# Filtro.net
KiCad netlist of a schematic drawn in Altium Designer
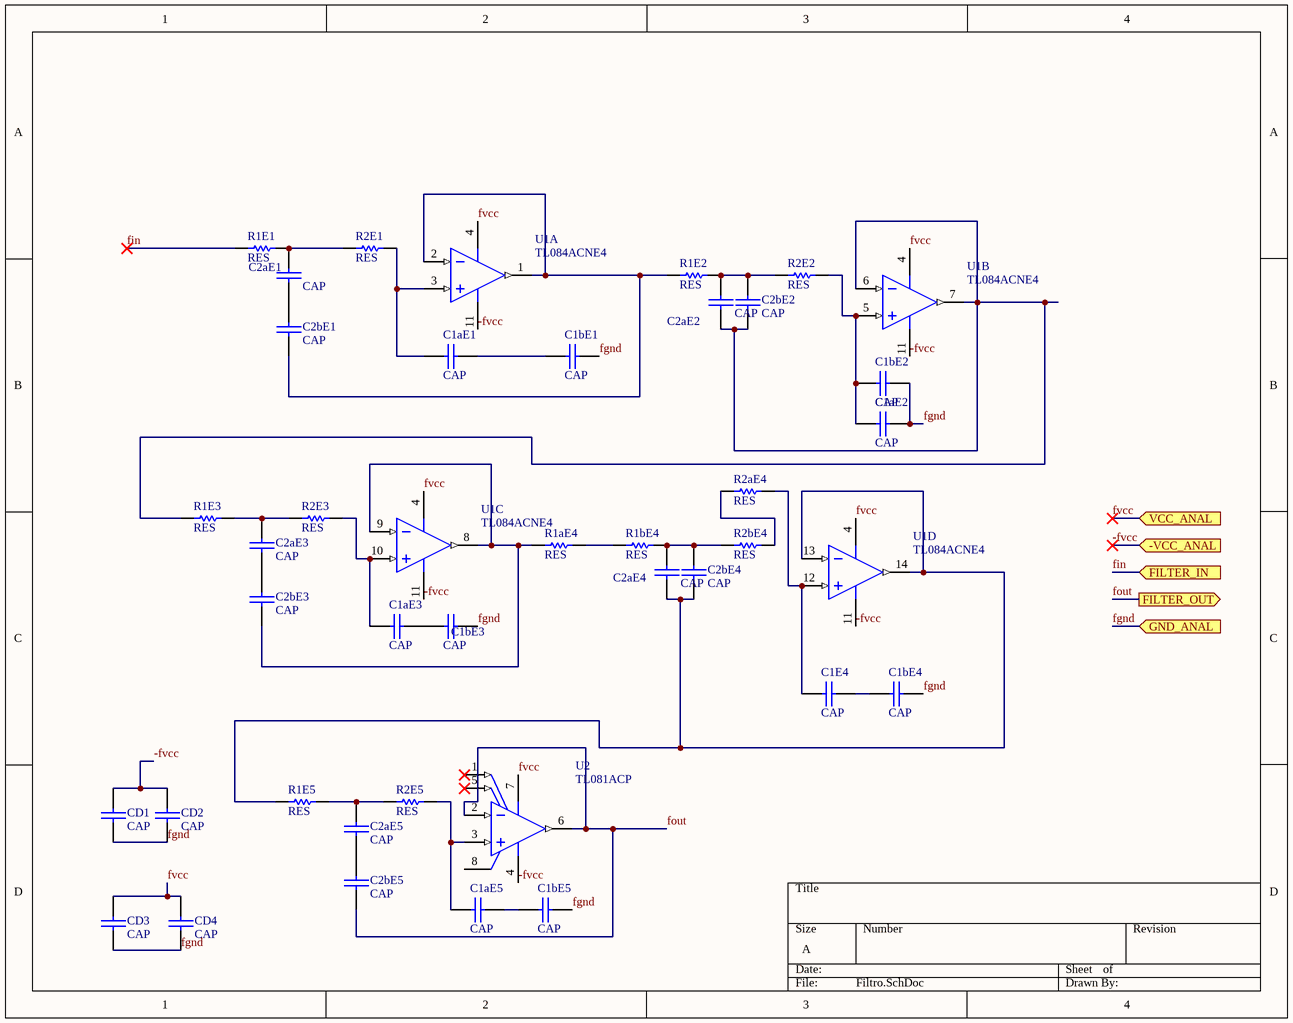
[diagram p0: Filtro.SchDoc]

(export (version "E")
  (design (tool "Eeschema 10.0.6"))
  (components
    (comp (ref "C1aE1") (value "CAP") (footprint "0805") (libsource (lib "LIB PIO IX") (part "CAP")))
    (comp (ref "C1aE2") (value "CAP") (footprint "0805") (libsource (lib "LIB PIO IX") (part "CAP")))
    (comp (ref "C1aE3") (value "CAP") (footprint "0805") (libsource (lib "LIB PIO IX") (part "CAP")))
    (comp (ref "C1aE5") (value "CAP") (footprint "0805") (libsource (lib "LIB PIO IX") (part "CAP")))
    (comp (ref "C1bE1") (value "CAP") (footprint "0805") (libsource (lib "LIB PIO IX") (part "CAP")))
    (comp (ref "C1bE2") (value "CAP") (footprint "0805") (libsource (lib "LIB PIO IX") (part "CAP")))
    (comp (ref "C1bE3") (value "CAP") (footprint "0805") (libsource (lib "LIB PIO IX") (part "CAP")))
    (comp (ref "C1bE4") (value "CAP") (footprint "0805") (libsource (lib "LIB PIO IX") (part "CAP")))
    (comp (ref "C1bE5") (value "CAP") (footprint "0805") (libsource (lib "LIB PIO IX") (part "CAP")))
    (comp (ref "C1E4") (value "CAP") (footprint "0805") (libsource (lib "LIB PIO IX") (part "CAP")))
    (comp (ref "C2aE1") (value "CAP") (footprint "0805") (libsource (lib "LIB PIO IX") (part "CAP")))
    (comp (ref "C2aE2") (value "CAP") (footprint "0805") (libsource (lib "LIB PIO IX") (part "CAP")))
    (comp (ref "C2aE3") (value "CAP") (footprint "0805") (libsource (lib "LIB PIO IX") (part "CAP")))
    (comp (ref "C2aE4") (value "CAP") (footprint "0805") (libsource (lib "LIB PIO IX") (part "CAP")))
    (comp (ref "C2aE5") (value "CAP") (footprint "0805") (libsource (lib "LIB PIO IX") (part "CAP")))
    (comp (ref "C2bE1") (value "CAP") (footprint "0805") (libsource (lib "LIB PIO IX") (part "CAP")))
    (comp (ref "C2bE2") (value "CAP") (footprint "0805") (libsource (lib "LIB PIO IX") (part "CAP")))
    (comp (ref "C2bE3") (value "CAP") (footprint "0805") (libsource (lib "LIB PIO IX") (part "CAP")))
    (comp (ref "C2bE4") (value "CAP") (footprint "0805") (libsource (lib "LIB PIO IX") (part "CAP")))
    (comp (ref "C2bE5") (value "CAP") (footprint "0805") (libsource (lib "LIB PIO IX") (part "CAP")))
    (comp (ref "CD1") (value "CAP") (footprint "0805") (libsource (lib "LIB PIO IX") (part "CAP")))
    (comp (ref "CD2") (value "CAP") (footprint "0805") (libsource (lib "LIB PIO IX") (part "CAP")))
    (comp (ref "CD3") (value "CAP") (footprint "0805") (libsource (lib "LIB PIO IX") (part "CAP")))
    (comp (ref "CD4") (value "CAP") (footprint "0805") (libsource (lib "LIB PIO IX") (part "CAP")))
    (comp (ref "R1aE4") (value "RES") (footprint "0805") (libsource (lib "LIB PIO IX") (part "RES")))
    (comp (ref "R1bE4") (value "RES") (footprint "0805") (libsource (lib "LIB PIO IX") (part "RES")))
    (comp (ref "R1E1") (value "RES") (footprint "0805") (libsource (lib "LIB PIO IX") (part "RES")))
    (comp (ref "R1E2") (value "RES") (footprint "0805") (libsource (lib "LIB PIO IX") (part "RES")))
    (comp (ref "R1E3") (value "RES") (footprint "0805") (libsource (lib "LIB PIO IX") (part "RES")))
    (comp (ref "R1E5") (value "RES") (footprint "0805") (libsource (lib "LIB PIO IX") (part "RES")))
    (comp (ref "R2aE4") (value "RES") (footprint "0805") (libsource (lib "LIB PIO IX") (part "RES")))
    (comp (ref "R2bE4") (value "RES") (footprint "0805") (libsource (lib "LIB PIO IX") (part "RES")))
    (comp (ref "R2E1") (value "RES") (footprint "0805") (libsource (lib "LIB PIO IX") (part "RES")))
    (comp (ref "R2E2") (value "RES") (footprint "0805") (libsource (lib "LIB PIO IX") (part "RES")))
    (comp (ref "R2E3") (value "RES") (footprint "0805") (libsource (lib "LIB PIO IX") (part "RES")))
    (comp (ref "R2E5") (value "RES") (footprint "0805") (libsource (lib "LIB PIO IX") (part "RES")))
    (comp (ref "U1")
      (value "TL084ACNE4")
      (footprint "TI-N14")
      (description "JFET-Input Operational Amplifier, 7 to 36 V, 0 to 70 degC, 14-pin DIP (N14), Pb-Free (RoHS)")
      (fields (field (name "MANUFACTURER") "Texas Instruments"))
      (libsource (lib "TI Amplifiers and Linear Operational Amplifier General Purpose") (part "TL084ACNE4"))
    )
    (comp (ref "U2")
      (value "TL081ACP")
      (footprint "TI-P8")
      (description "JFET-Input Operational Amplifier, 7 to 36 V, 0 to 70 degC, 8-pin DIP (P8), Pb-Free (RoHS)")
      (fields (field (name "MANUFACTURER") "Texas Instruments"))
      (libsource (lib "TI Amplifiers and Linear Operational Amplifier General Purpose") (part "TL081ACP"))
    )
  )
  (nets
    (net (code "1") (name "/-fvcc") (class "Default")
      (node (ref "CD1") (pin "1") (pinfunction "1_1") (pintype "passive"))
      (node (ref "CD2") (pin "1") (pinfunction "1_1") (pintype "passive"))
      (node (ref "U1") (pin "11") (pinfunction "VCC-_11") (pintype "power_in"))
      (node (ref "U2") (pin "4") (pinfunction "VCC-_4") (pintype "power_in"))
    )
    (net (code "2") (name "/fgnd") (class "Default")
      (node (ref "C1aE2") (pin "2") (pinfunction "2_2") (pintype "passive"))
      (node (ref "C1bE1") (pin "2") (pinfunction "2_2") (pintype "passive"))
      (node (ref "C1bE2") (pin "2") (pinfunction "2_2") (pintype "passive"))
      (node (ref "C1bE3") (pin "2") (pinfunction "2_2") (pintype "passive"))
      (node (ref "C1bE4") (pin "2") (pinfunction "2_2") (pintype "passive"))
      (node (ref "C1bE5") (pin "2") (pinfunction "2_2") (pintype "passive"))
      (node (ref "CD1") (pin "2") (pinfunction "2_2") (pintype "passive"))
      (node (ref "CD2") (pin "2") (pinfunction "2_2") (pintype "passive"))
      (node (ref "CD3") (pin "2") (pinfunction "2_2") (pintype "passive"))
      (node (ref "CD4") (pin "2") (pinfunction "2_2") (pintype "passive"))
    )
    (net (code "3") (name "/fin") (class "Default")
      (node (ref "R1E1") (pin "1") (pinfunction "1_1") (pintype "passive+no_connect"))
    )
    (net (code "4") (name "/fout") (class "Default")
      (node (ref "C2bE5") (pin "2") (pinfunction "2_2") (pintype "passive"))
      (node (ref "U2") (pin "2") (pinfunction "IN-_2") (pintype "input"))
      (node (ref "U2") (pin "6") (pinfunction "OUT_6") (pintype "output"))
    )
    (net (code "5") (name "/fvcc") (class "Default")
      (node (ref "CD3") (pin "1") (pinfunction "1_1") (pintype "passive"))
      (node (ref "CD4") (pin "1") (pinfunction "1_1") (pintype "passive"))
      (node (ref "U1") (pin "4") (pinfunction "VCC+_4") (pintype "power_in"))
      (node (ref "U2") (pin "7") (pinfunction "VCC+_7") (pintype "power_in"))
    )
    (net (code "6") (name "Net-(C1E4-Pad2)") (class "Default")
      (node (ref "C1E4") (pin "2") (pinfunction "2_2") (pintype "passive"))
      (node (ref "C1bE4") (pin "1") (pinfunction "1_1") (pintype "passive"))
    )
    (net (code "7") (name "Net-(C1aE1-Pad2)") (class "Default")
      (node (ref "C1aE1") (pin "2") (pinfunction "2_2") (pintype "passive"))
      (node (ref "C1bE1") (pin "1") (pinfunction "1_1") (pintype "passive"))
    )
    (net (code "8") (name "Net-(C1aE3-Pad2)") (class "Default")
      (node (ref "C1aE3") (pin "2") (pinfunction "2_2") (pintype "passive"))
      (node (ref "C1bE3") (pin "1") (pinfunction "1_1") (pintype "passive"))
    )
    (net (code "9") (name "Net-(C1aE5-Pad2)") (class "Default")
      (node (ref "C1aE5") (pin "2") (pinfunction "2_2") (pintype "passive"))
      (node (ref "C1bE5") (pin "1") (pinfunction "1_1") (pintype "passive"))
    )
    (net (code "10") (name "Net-(C2aE1-Pad1)") (class "Default")
      (node (ref "C2aE1") (pin "1") (pinfunction "1_1") (pintype "passive"))
      (node (ref "R1E1") (pin "2") (pinfunction "2_2") (pintype "passive"))
      (node (ref "R2E1") (pin "1") (pinfunction "1_1") (pintype "passive"))
    )
    (net (code "11") (name "Net-(C2aE1-Pad2)") (class "Default")
      (node (ref "C2aE1") (pin "2") (pinfunction "2_2") (pintype "passive"))
      (node (ref "C2bE1") (pin "1") (pinfunction "1_1") (pintype "passive"))
    )
    (net (code "12") (name "Net-(C2aE2-Pad1)") (class "Default")
      (node (ref "C2aE2") (pin "1") (pinfunction "1_1") (pintype "passive"))
      (node (ref "C2bE2") (pin "1") (pinfunction "1_1") (pintype "passive"))
      (node (ref "R1E2") (pin "2") (pinfunction "2_2") (pintype "passive"))
      (node (ref "R2E2") (pin "1") (pinfunction "1_1") (pintype "passive"))
    )
    (net (code "13") (name "Net-(C2aE3-Pad1)") (class "Default")
      (node (ref "C2aE3") (pin "1") (pinfunction "1_1") (pintype "passive"))
      (node (ref "R1E3") (pin "2") (pinfunction "2_2") (pintype "passive"))
      (node (ref "R2E3") (pin "1") (pinfunction "1_1") (pintype "passive"))
    )
    (net (code "14") (name "Net-(C2aE3-Pad2)") (class "Default")
      (node (ref "C2aE3") (pin "2") (pinfunction "2_2") (pintype "passive"))
      (node (ref "C2bE3") (pin "1") (pinfunction "1_1") (pintype "passive"))
    )
    (net (code "15") (name "Net-(C2aE4-Pad1)") (class "Default")
      (node (ref "C2aE4") (pin "1") (pinfunction "1_1") (pintype "passive"))
      (node (ref "C2bE4") (pin "1") (pinfunction "1_1") (pintype "passive"))
      (node (ref "R1bE4") (pin "2") (pinfunction "2_2") (pintype "passive"))
      (node (ref "R2bE4") (pin "1") (pinfunction "1_1") (pintype "passive"))
    )
    (net (code "16") (name "Net-(C2aE5-Pad1)") (class "Default")
      (node (ref "C2aE5") (pin "1") (pinfunction "1_1") (pintype "passive"))
      (node (ref "R1E5") (pin "2") (pinfunction "2_2") (pintype "passive"))
      (node (ref "R2E5") (pin "1") (pinfunction "1_1") (pintype "passive"))
    )
    (net (code "17") (name "Net-(C2aE5-Pad2)") (class "Default")
      (node (ref "C2aE5") (pin "2") (pinfunction "2_2") (pintype "passive"))
      (node (ref "C2bE5") (pin "1") (pinfunction "1_1") (pintype "passive"))
    )
    (net (code "18") (name "Net-(R1aE4-Pad2)") (class "Default")
      (node (ref "R1aE4") (pin "2") (pinfunction "2_2") (pintype "passive"))
      (node (ref "R1bE4") (pin "1") (pinfunction "1_1") (pintype "passive"))
    )
    (net (code "19") (name "Net-(R2aE4-Pad1)") (class "Default")
      (node (ref "R2aE4") (pin "1") (pinfunction "1_1") (pintype "passive"))
      (node (ref "R2bE4") (pin "2") (pinfunction "2_2") (pintype "passive"))
    )
    (net (code "20") (name "Net-(U1A-IN1+)") (class "Default")
      (node (ref "C1aE1") (pin "1") (pinfunction "1_1") (pintype "passive"))
      (node (ref "R2E1") (pin "2") (pinfunction "2_2") (pintype "passive"))
      (node (ref "U1") (pin "3") (pinfunction "IN1+_3") (pintype "input"))
    )
    (net (code "21") (name "Net-(U1A-IN1-)") (class "Default")
      (node (ref "C2bE1") (pin "2") (pinfunction "2_2") (pintype "passive"))
      (node (ref "R1E2") (pin "1") (pinfunction "1_1") (pintype "passive"))
      (node (ref "U1") (pin "1") (pinfunction "OUT1_1") (pintype "output"))
      (node (ref "U1") (pin "2") (pinfunction "IN1-_2") (pintype "input"))
    )
    (net (code "22") (name "Net-(U1B-IN2+)") (class "Default")
      (node (ref "C1aE2") (pin "1") (pinfunction "1_1") (pintype "passive"))
      (node (ref "C1bE2") (pin "1") (pinfunction "1_1") (pintype "passive"))
      (node (ref "R2E2") (pin "2") (pinfunction "2_2") (pintype "passive"))
      (node (ref "U1") (pin "5") (pinfunction "IN2+_5") (pintype "input"))
    )
    (net (code "23") (name "Net-(U1B-IN2-)") (class "Default")
      (node (ref "C2aE2") (pin "2") (pinfunction "2_2") (pintype "passive"))
      (node (ref "C2bE2") (pin "2") (pinfunction "2_2") (pintype "passive"))
      (node (ref "R1E3") (pin "1") (pinfunction "1_1") (pintype "passive"))
      (node (ref "U1") (pin "6") (pinfunction "IN2-_6") (pintype "input"))
      (node (ref "U1") (pin "7") (pinfunction "OUT2_7") (pintype "output"))
    )
    (net (code "24") (name "Net-(U1C-IN3+)") (class "Default")
      (node (ref "C1aE3") (pin "1") (pinfunction "1_1") (pintype "passive"))
      (node (ref "R2E3") (pin "2") (pinfunction "2_2") (pintype "passive"))
      (node (ref "U1") (pin "10") (pinfunction "IN3+_10") (pintype "input"))
    )
    (net (code "25") (name "Net-(U1C-IN3-)") (class "Default")
      (node (ref "C2bE3") (pin "2") (pinfunction "2_2") (pintype "passive"))
      (node (ref "R1aE4") (pin "1") (pinfunction "1_1") (pintype "passive"))
      (node (ref "U1") (pin "8") (pinfunction "OUT3_8") (pintype "output"))
      (node (ref "U1") (pin "9") (pinfunction "IN3-_9") (pintype "input"))
    )
    (net (code "26") (name "Net-(U1D-IN4+)") (class "Default")
      (node (ref "C1E4") (pin "1") (pinfunction "1_1") (pintype "passive"))
      (node (ref "R2aE4") (pin "2") (pinfunction "2_2") (pintype "passive"))
      (node (ref "U1") (pin "12") (pinfunction "IN4+_12") (pintype "input"))
    )
    (net (code "27") (name "Net-(U1D-IN4-)") (class "Default")
      (node (ref "C2aE4") (pin "2") (pinfunction "2_2") (pintype "passive"))
      (node (ref "C2bE4") (pin "2") (pinfunction "2_2") (pintype "passive"))
      (node (ref "R1E5") (pin "1") (pinfunction "1_1") (pintype "passive"))
      (node (ref "U1") (pin "13") (pinfunction "IN4-_13") (pintype "input"))
      (node (ref "U1") (pin "14") (pinfunction "OUT4_14") (pintype "output"))
    )
    (net (code "28") (name "Net-(U2-IN+)") (class "Default")
      (node (ref "C1aE5") (pin "1") (pinfunction "1_1") (pintype "passive"))
      (node (ref "R2E5") (pin "2") (pinfunction "2_2") (pintype "passive"))
      (node (ref "U2") (pin "3") (pinfunction "IN+_3") (pintype "input"))
    )
    (net (code "29") (name "unconnected-(U2-NC-Pad8)") (class "Default")
      (node (ref "U2") (pin "8") (pinfunction "NC_8") (pintype "passive"))
    )
    (net (code "30") (name "unconnected-(U2-OFFSET_N1-Pad1)") (class "Default")
      (node (ref "U2") (pin "1") (pinfunction "OFFSET_N1_1") (pintype "input+no_connect"))
    )
    (net (code "31") (name "unconnected-(U2-OFFSET_N2-Pad5)") (class "Default")
      (node (ref "U2") (pin "5") (pinfunction "OFFSET_N2_5") (pintype "input+no_connect"))
    )
  )
)
